# expander_board_rev1_1.net
KiCad netlist of a schematic drawn in EAGLE
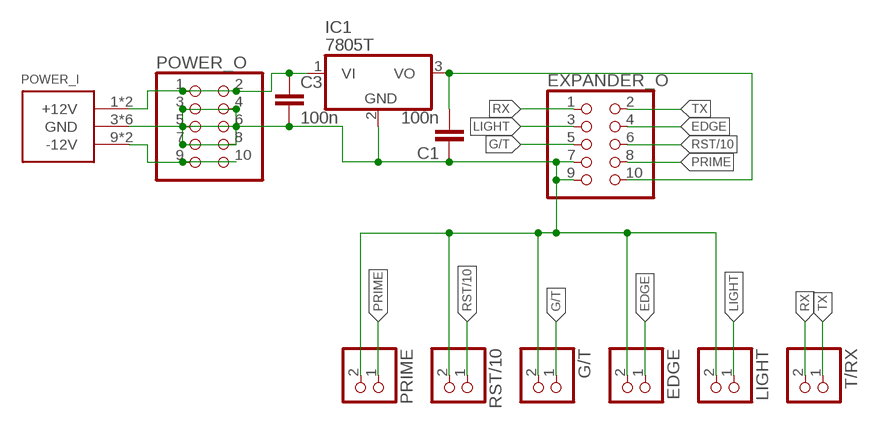
[diagram p0: schematic, sheet 1]

(export (version "E")
  (design (tool "Eeschema 10.0.6"))
  (components
    (comp (ref "C1")
      (value "100n")
      (footprint "eagle-import:C025-025X050")
      (libsource (lib "eagle-import") (part "C-EU025-025X050"))
    )
    (comp (ref "C3")
      (value "100n")
      (footprint "eagle-import:C025-025X050")
      (libsource (lib "eagle-import") (part "C-EU025-025X050"))
    )
    (comp (ref "EDGE")
      (value "PINHD-1X2")
      (footprint "eagle-import:1X02")
      (libsource (lib "eagle-import") (part "PINHD-1X2"))
    )
    (comp (ref "EXPANDER_O")
      (value "PINHD-2X5")
      (footprint "eagle-import:2X05")
      (libsource (lib "eagle-import") (part "PINHD-2X5"))
    )
    (comp (ref "G/T")
      (value "PINHD-1X2")
      (footprint "eagle-import:1X02")
      (libsource (lib "eagle-import") (part "PINHD-1X2"))
    )
    (comp (ref "IC1")
      (value "7805T")
      (footprint "eagle-import:TO220H")
      (libsource (lib "eagle-import") (part "78T05"))
    )
    (comp (ref "LIGHT")
      (value "PINHD-1X2")
      (footprint "eagle-import:1X02")
      (libsource (lib "eagle-import") (part "PINHD-1X2"))
    )
    (comp (ref "POWER_I")
      (value "POWER_SIMPLE")
      (footprint "eagle-import:POWER_10_NSTRIPE")
      (libsource (lib "eagle-import") (part "POWER_SIMPLE"))
    )
    (comp (ref "POWER_O")
      (value "PINHD-2X5")
      (footprint "eagle-import:2X05")
      (libsource (lib "eagle-import") (part "PINHD-2X5"))
    )
    (comp (ref "PRIME")
      (value "PINHD-1X2")
      (footprint "eagle-import:1X02")
      (libsource (lib "eagle-import") (part "PINHD-1X2"))
    )
    (comp (ref "RST/10")
      (value "PINHD-1X2")
      (footprint "eagle-import:1X02")
      (libsource (lib "eagle-import") (part "PINHD-1X2"))
    )
    (comp (ref "T/RX")
      (value "PINHD-1X2")
      (footprint "eagle-import:1X02")
      (libsource (lib "eagle-import") (part "PINHD-1X2"))
    )
  )
  (nets
    (net (code "1") (name "EDGE") (class "Default")
      (node (ref "EDGE") (pin "1") (pinfunction "1_1") (pintype "passive"))
      (node (ref "EXPANDER_O") (pin "4") (pinfunction "4_4") (pintype "passive"))
    )
    (net (code "2") (name "G{slash}T") (class "Default")
      (node (ref "EXPANDER_O") (pin "5") (pinfunction "5_5") (pintype "passive"))
      (node (ref "G/T") (pin "1") (pinfunction "1_1") (pintype "passive"))
    )
    (net (code "3") (name "LIGHT") (class "Default")
      (node (ref "EXPANDER_O") (pin "3") (pinfunction "3_3") (pintype "passive"))
      (node (ref "LIGHT") (pin "1") (pinfunction "1_1") (pintype "passive"))
    )
    (net (code "4") (name "Net-(IC1-GND)") (class "Default")
      (node (ref "C1") (pin "1") (pinfunction "1_1") (pintype "passive"))
      (node (ref "C3") (pin "2") (pinfunction "2_2") (pintype "passive"))
      (node (ref "EDGE") (pin "2") (pinfunction "2_2") (pintype "passive"))
      (node (ref "EXPANDER_O") (pin "7") (pinfunction "7_7") (pintype "passive"))
      (node (ref "EXPANDER_O") (pin "9") (pinfunction "9_9") (pintype "passive"))
      (node (ref "G/T") (pin "2") (pinfunction "2_2") (pintype "passive"))
      (node (ref "IC1") (pin "2") (pinfunction "GND_2") (pintype "passive"))
      (node (ref "LIGHT") (pin "2") (pinfunction "2_2") (pintype "passive"))
      (node (ref "POWER_I") (pin "3") (pinfunction "GND_3") (pintype "bidirectional"))
      (node (ref "POWER_I") (pin "4") (pinfunction "GND_4") (pintype "bidirectional"))
      (node (ref "POWER_I") (pin "5") (pinfunction "GND_5") (pintype "bidirectional"))
      (node (ref "POWER_I") (pin "6") (pinfunction "GND_6") (pintype "bidirectional"))
      (node (ref "POWER_I") (pin "7") (pinfunction "GND_7") (pintype "bidirectional"))
      (node (ref "POWER_I") (pin "8") (pinfunction "GND_8") (pintype "bidirectional"))
      (node (ref "POWER_O") (pin "3") (pinfunction "3_3") (pintype "passive"))
      (node (ref "POWER_O") (pin "4") (pinfunction "4_4") (pintype "passive"))
      (node (ref "POWER_O") (pin "5") (pinfunction "5_5") (pintype "passive"))
      (node (ref "POWER_O") (pin "6") (pinfunction "6_6") (pintype "passive"))
      (node (ref "POWER_O") (pin "7") (pinfunction "7_7") (pintype "passive"))
      (node (ref "POWER_O") (pin "8") (pinfunction "8_8") (pintype "passive"))
      (node (ref "PRIME") (pin "2") (pinfunction "2_2") (pintype "passive"))
      (node (ref "RST/10") (pin "2") (pinfunction "2_2") (pintype "passive"))
    )
    (net (code "5") (name "Net-(IC1-VI)") (class "Default")
      (node (ref "C3") (pin "1") (pinfunction "1_1") (pintype "passive"))
      (node (ref "IC1") (pin "1") (pinfunction "VI_1") (pintype "input"))
      (node (ref "POWER_I") (pin "1") (pinfunction "+12V_1") (pintype "bidirectional"))
      (node (ref "POWER_I") (pin "2") (pinfunction "+12V_2") (pintype "bidirectional"))
      (node (ref "POWER_O") (pin "1") (pinfunction "1_1") (pintype "passive"))
      (node (ref "POWER_O") (pin "2") (pinfunction "2_2") (pintype "passive"))
    )
    (net (code "6") (name "Net-(IC1-VO)") (class "Default")
      (node (ref "C1") (pin "2") (pinfunction "2_2") (pintype "passive"))
      (node (ref "EXPANDER_O") (pin "10") (pinfunction "10_10") (pintype "passive"))
      (node (ref "IC1") (pin "3") (pinfunction "VO_3") (pintype "passive"))
    )
    (net (code "7") (name "Net-(POWER_I--12V-Pad10)") (class "Default")
      (node (ref "POWER_I") (pin "10") (pinfunction "-12V_10") (pintype "bidirectional"))
      (node (ref "POWER_I") (pin "9") (pinfunction "-12V_9") (pintype "bidirectional"))
      (node (ref "POWER_O") (pin "10") (pinfunction "10_10") (pintype "passive"))
      (node (ref "POWER_O") (pin "9") (pinfunction "9_9") (pintype "passive"))
    )
    (net (code "8") (name "PRIME") (class "Default")
      (node (ref "EXPANDER_O") (pin "8") (pinfunction "8_8") (pintype "passive"))
      (node (ref "PRIME") (pin "1") (pinfunction "1_1") (pintype "passive"))
    )
    (net (code "9") (name "RST{slash}10") (class "Default")
      (node (ref "EXPANDER_O") (pin "6") (pinfunction "6_6") (pintype "passive"))
      (node (ref "RST/10") (pin "1") (pinfunction "1_1") (pintype "passive"))
    )
    (net (code "10") (name "RX") (class "Default")
      (node (ref "EXPANDER_O") (pin "1") (pinfunction "1_1") (pintype "passive"))
      (node (ref "T/RX") (pin "2") (pinfunction "2_2") (pintype "passive"))
    )
    (net (code "11") (name "TX") (class "Default")
      (node (ref "EXPANDER_O") (pin "2") (pinfunction "2_2") (pintype "passive"))
      (node (ref "T/RX") (pin "1") (pinfunction "1_1") (pintype "passive"))
    )
  )
)
